# LCD_TouchBackLight.net
KiCad netlist of a schematic drawn in Altium Designer
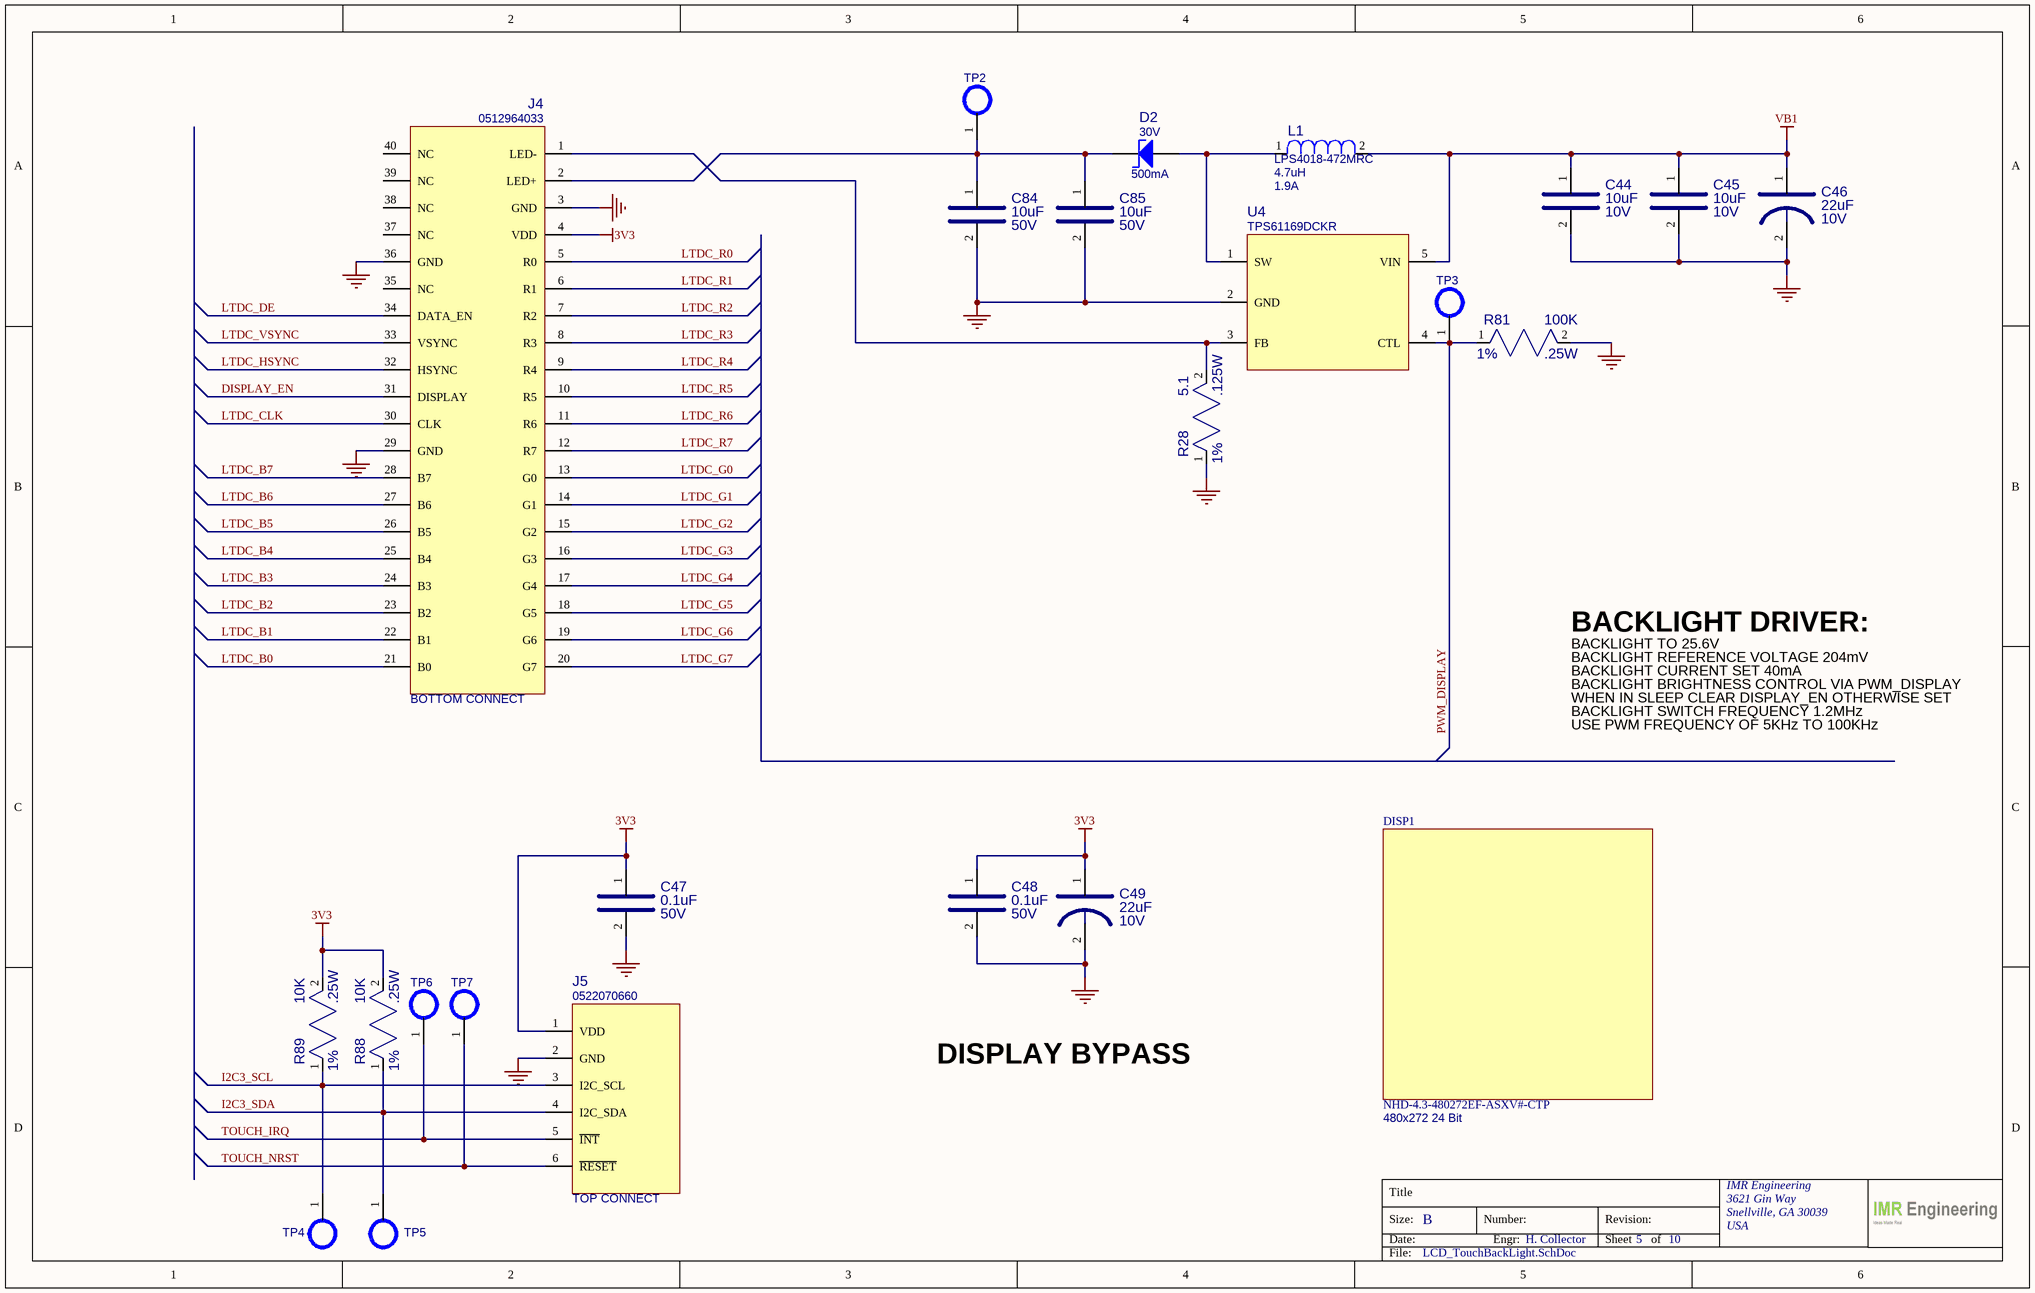
[diagram p0: LCD_TouchBackLight.SchDoc]

(export (version "E")
  (design (tool "Eeschema 10.0.6"))
  (components
    (comp (ref "C44")
      (value "10uF")
      (footprint "CAP_0805")
      (description "CAP CER 10UF 10V X7R 0805")
      (fields
        (field (name "MFG") "TDK Corporation")
        (field (name "TOLERANCE") "10%")
        (field (name "VOLTAGE") "10V")
      )
      (libsource (lib "IMR_Lib") (part "CAP_10UF_10V_0805"))
    )
    (comp (ref "C45")
      (value "10uF")
      (footprint "CAP_0805")
      (description "CAP CER 10UF 10V X7R 0805")
      (fields
        (field (name "MFG") "TDK Corporation")
        (field (name "TOLERANCE") "10%")
        (field (name "VOLTAGE") "10V")
      )
      (libsource (lib "IMR_Lib") (part "CAP_10UF_10V_0805"))
    )
    (comp (ref "C46")
      (value "22uF")
      (footprint "CAP_1206_TANT")
      (description "CAP TANT 22UF 20% 10V 1206")
      (fields
        (field (name "MFG") "AVX Corporation")
        (field (name "TOLERANCE") "10%")
        (field (name "VOLTAGE") "10V")
      )
      (libsource (lib "IMR_Lib") (part "CAP_22UF_10V_TANT"))
    )
    (comp (ref "C47")
      (value "0.1uF")
      (footprint "CAP_0805")
      (description "CAP CER 0.1UF 50V X7R 0805")
      (fields (field (name "MFG") "AVX") (field (name "TOLERANCE") "10%") (field (name "VOLTAGE") "50V"))
      (libsource (lib "IMR_Lib") (part "CAP_0.1UF_50V_0805"))
    )
    (comp (ref "C48")
      (value "0.1uF")
      (footprint "CAP_0805")
      (description "CAP CER 0.1UF 50V X7R 0805")
      (fields (field (name "MFG") "AVX") (field (name "TOLERANCE") "10%") (field (name "VOLTAGE") "50V"))
      (libsource (lib "IMR_Lib") (part "CAP_0.1UF_50V_0805"))
    )
    (comp (ref "C49")
      (value "22uF")
      (footprint "CAP_1206_TANT")
      (description "CAP TANT 22UF 20% 10V 1206")
      (fields
        (field (name "MFG") "AVX Corporation")
        (field (name "TOLERANCE") "10%")
        (field (name "VOLTAGE") "10V")
      )
      (libsource (lib "IMR_Lib") (part "CAP_22UF_10V_TANT"))
    )
    (comp (ref "C84")
      (value "10uF")
      (footprint "CAP_1206")
      (description "CAP CER 10UF 50V X5R 1206")
      (fields
        (field (name "MFG") "Samsung Electro-Mechanics")
        (field (name "TOLERANCE") "10%")
        (field (name "VOLTAGE") "50V")
      )
      (libsource (lib "IMR_Lib") (part "CAP_10UF_50V_1206"))
    )
    (comp (ref "C85")
      (value "10uF")
      (footprint "CAP_1206")
      (description "CAP CER 10UF 50V X5R 1206")
      (fields
        (field (name "MFG") "Samsung Electro-Mechanics")
        (field (name "TOLERANCE") "10%")
        (field (name "VOLTAGE") "50V")
      )
      (libsource (lib "IMR_Lib") (part "CAP_10UF_50V_1206"))
    )
    (comp (ref "D2")
      (value "30V")
      (footprint "SOD123")
      (description "DIODE SCHOTTKY 30V 500MA SOD123")
      (fields
        (field (name "MFG") "Nexperia USA Inc.")
        (field (name "CURRENT") "500mA")
        (field (name "Comment") "PMEG3005EGWJ")
      )
      (libsource (lib "IMR_Lib") (part "DIODE_SCHOTTKY_PMEG3005EGWJ"))
    )
    (comp (ref "DISP1")
      (value "NHD-4.3-480272EF-ASXV#-CTP")
      (footprint "NHD_NHD-4.3-480272EF-ASXV#-CTP")
      (description "LCD TFT 480X272 HIGH BRIGHT")
      (fields (field (name "MFG") "Newhaven Display Intl") (field (name "ALTIUM_VALUE") "480x272 24 Bit"))
      (libsource (lib "IMR_Lib") (part "MODULE_NHD-4.3-480272EF-ASXV#-CTP"))
    )
    (comp (ref "J4")
      (value "0512964033")
      (footprint "CONN_MOLEX_0512964033")
      (description "CONN FFC BOTTOM 40POS 0.50MM R/A")
      (fields (field (name "MFG") "Molex") (field (name "ALTIUM_VALUE") "BOTTOM CONNECT"))
      (libsource (lib "IMR_Lib") (part "CONN_MOLEX_0512964033"))
    )
    (comp (ref "J5")
      (value "0522070660")
      (footprint "CONN_MOLEX_0522070660")
      (description "CONN FPC TOP 6POS 1.00MM R/A")
      (fields (field (name "MFG") "Molex") (field (name "ALTIUM_VALUE") "TOP CONNECT"))
      (libsource (lib "IMR_Lib") (part "CONN_MOLEX_0522070660"))
    )
    (comp (ref "L1")
      (value "4.7uH")
      (footprint "LPS4018")
      (description "SHIELDED POWER INDUCTORS, 4.7UH")
      (fields
        (field (name "MFG") "COILCRAFT")
        (field (name "TOLERANCE") "20%")
        (field (name "MFG_PN") "LPS4018-472MRC")
        (field (name "CURRENT") "1.9A")
      )
      (libsource (lib "IMR_Lib") (part "INDUCTOR_LPS4018-472MRC"))
    )
    (comp (ref "R28")
      (value "5.1")
      (footprint "PMG_RES_0805")
      (description "RES 5.1 OHM 1% 1/8W 0805")
      (fields
        (field (name "MFG") "Yageo")
        (field (name "TOLERANCE") "1%")
        (field (name "POWER") ".125W")
        (field (name "Comment") "RC0805FR-075R1L")
      )
      (libsource (lib "IMR_Lib") (part "RES_5.1_0805_1/8W_1%"))
    )
    (comp (ref "R81")
      (value "100K")
      (footprint "PMG_RES_0805")
      (description "RES SMD 100K OHM 1% 1/4W 0805")
      (fields
        (field (name "MFG") "KOA Speer Electronics, Inc.")
        (field (name "TOLERANCE") "1%")
        (field (name "POWER") ".25W")
        (field (name "Comment") "RK73H2ATTD1003F")
      )
      (libsource (lib "IMR_Lib") (part "RES_100K_0805_1/4W_1%"))
    )
    (comp (ref "R88")
      (value "10K")
      (footprint "RES_0805")
      (description "RES SMD 10K OHM 1% 1/4W 0805")
      (fields
        (field (name "MFG") "KOA Speer Electronics, Inc.")
        (field (name "TOLERANCE") "1%")
        (field (name "POWER") ".25W")
        (field (name "Comment") "SG73S2ATTD1002F")
      )
      (libsource (lib "IMR_Lib") (part "RES_10K_0805_1/4W_1%"))
    )
    (comp (ref "R89")
      (value "10K")
      (footprint "RES_0805")
      (description "RES SMD 10K OHM 1% 1/4W 0805")
      (fields
        (field (name "MFG") "KOA Speer Electronics, Inc.")
        (field (name "TOLERANCE") "1%")
        (field (name "POWER") ".25W")
        (field (name "Comment") "SG73S2ATTD1002F")
      )
      (libsource (lib "IMR_Lib") (part "RES_10K_0805_1/4W_1%"))
    )
    (comp (ref "TP2")
      (value "TP_0635MM_HOLE")
      (footprint "TP_0635MM_HOLE")
      (description "3MM IN D. MT HOLE")
      (libsource (lib "IMR_Lib") (part "TP_0635MM_HOLE"))
    )
    (comp (ref "TP3")
      (value "TP_0635MM_HOLE")
      (footprint "TP_0635MM_HOLE")
      (description "3MM IN D. MT HOLE")
      (libsource (lib "IMR_Lib") (part "TP_0635MM_HOLE"))
    )
    (comp (ref "TP4")
      (value "TP_0635MM_HOLE")
      (footprint "TP_0635MM_HOLE")
      (description "3MM IN D. MT HOLE")
      (libsource (lib "IMR_Lib") (part "TP_0635MM_HOLE"))
    )
    (comp (ref "TP5")
      (value "TP_0635MM_HOLE")
      (footprint "TP_0635MM_HOLE")
      (description "3MM IN D. MT HOLE")
      (libsource (lib "IMR_Lib") (part "TP_0635MM_HOLE"))
    )
    (comp (ref "TP6")
      (value "TP_0635MM_HOLE")
      (footprint "TP_0635MM_HOLE")
      (description "3MM IN D. MT HOLE")
      (libsource (lib "IMR_Lib") (part "TP_0635MM_HOLE"))
    )
    (comp (ref "TP7")
      (value "TP_0635MM_HOLE")
      (footprint "TP_0635MM_HOLE")
      (description "3MM IN D. MT HOLE")
      (libsource (lib "IMR_Lib") (part "TP_0635MM_HOLE"))
    )
    (comp (ref "U4")
      (value "TPS61169DCKR")
      (footprint "SC70-5_SOT-353_5-TSSOP")
      (description "IC LED DRVR RGLTR DIM 1.8A SC70")
      (fields (field (name "MFG") "Texas Instruments") (field (name "MFG_PN") "TPS61169DCKR"))
      (libsource (lib "IMR_Lib") (part "IC_TPS61169DCKR"))
    )
  )
  (nets
    (net (code "1") (name "/DISPLAY_EN") (class "Default")
      (node (ref "J4") (pin "31") (pinfunction "DISPLAY_31") (pintype "passive"))
    )
    (net (code "2") (name "/I2C3_SCL") (class "Default")
      (node (ref "J5") (pin "3") (pinfunction "I2C_SCL_3") (pintype "passive"))
      (node (ref "R89") (pin "1") (pinfunction "1_1") (pintype "passive"))
      (node (ref "TP4") (pin "1") (pinfunction "1_1") (pintype "passive"))
    )
    (net (code "3") (name "/I2C3_SDA") (class "Default")
      (node (ref "J5") (pin "4") (pinfunction "I2C_SDA_4") (pintype "passive"))
      (node (ref "R88") (pin "1") (pinfunction "1_1") (pintype "passive"))
      (node (ref "TP5") (pin "1") (pinfunction "1_1") (pintype "passive"))
    )
    (net (code "4") (name "/LTDC_B0") (class "Default")
      (node (ref "J4") (pin "21") (pinfunction "B0_21") (pintype "passive"))
    )
    (net (code "5") (name "/LTDC_B1") (class "Default")
      (node (ref "J4") (pin "22") (pinfunction "B1_22") (pintype "passive"))
    )
    (net (code "6") (name "/LTDC_B2") (class "Default")
      (node (ref "J4") (pin "23") (pinfunction "B2_23") (pintype "passive"))
    )
    (net (code "7") (name "/LTDC_B3") (class "Default")
      (node (ref "J4") (pin "24") (pinfunction "B3_24") (pintype "passive"))
    )
    (net (code "8") (name "/LTDC_B4") (class "Default")
      (node (ref "J4") (pin "25") (pinfunction "B4_25") (pintype "passive"))
    )
    (net (code "9") (name "/LTDC_B5") (class "Default")
      (node (ref "J4") (pin "26") (pinfunction "B5_26") (pintype "passive"))
    )
    (net (code "10") (name "/LTDC_B6") (class "Default")
      (node (ref "J4") (pin "27") (pinfunction "B6_27") (pintype "passive"))
    )
    (net (code "11") (name "/LTDC_B7") (class "Default")
      (node (ref "J4") (pin "28") (pinfunction "B7_28") (pintype "passive"))
    )
    (net (code "12") (name "/LTDC_CLK") (class "Default")
      (node (ref "J4") (pin "30") (pinfunction "CLK_30") (pintype "passive"))
    )
    (net (code "13") (name "/LTDC_DE") (class "Default")
      (node (ref "J4") (pin "34") (pinfunction "DATA_EN_34") (pintype "passive"))
    )
    (net (code "14") (name "/LTDC_G0") (class "Default")
      (node (ref "J4") (pin "13") (pinfunction "G0_13") (pintype "passive"))
    )
    (net (code "15") (name "/LTDC_G1") (class "Default")
      (node (ref "J4") (pin "14") (pinfunction "G1_14") (pintype "passive"))
    )
    (net (code "16") (name "/LTDC_G2") (class "Default")
      (node (ref "J4") (pin "15") (pinfunction "G2_15") (pintype "passive"))
    )
    (net (code "17") (name "/LTDC_G3") (class "Default")
      (node (ref "J4") (pin "16") (pinfunction "G3_16") (pintype "passive"))
    )
    (net (code "18") (name "/LTDC_G4") (class "Default")
      (node (ref "J4") (pin "17") (pinfunction "G4_17") (pintype "passive"))
    )
    (net (code "19") (name "/LTDC_G5") (class "Default")
      (node (ref "J4") (pin "18") (pinfunction "G5_18") (pintype "passive"))
    )
    (net (code "20") (name "/LTDC_G6") (class "Default")
      (node (ref "J4") (pin "19") (pinfunction "G6_19") (pintype "passive"))
    )
    (net (code "21") (name "/LTDC_G7") (class "Default")
      (node (ref "J4") (pin "20") (pinfunction "G7_20") (pintype "passive"))
    )
    (net (code "22") (name "/LTDC_HSYNC") (class "Default")
      (node (ref "J4") (pin "32") (pinfunction "HSYNC_32") (pintype "passive"))
    )
    (net (code "23") (name "/LTDC_R0") (class "Default")
      (node (ref "J4") (pin "5") (pinfunction "R0_5") (pintype "passive"))
    )
    (net (code "24") (name "/LTDC_R1") (class "Default")
      (node (ref "J4") (pin "6") (pinfunction "R1_6") (pintype "passive"))
    )
    (net (code "25") (name "/LTDC_R2") (class "Default")
      (node (ref "J4") (pin "7") (pinfunction "R2_7") (pintype "passive"))
    )
    (net (code "26") (name "/LTDC_R3") (class "Default")
      (node (ref "J4") (pin "8") (pinfunction "R3_8") (pintype "passive"))
    )
    (net (code "27") (name "/LTDC_R4") (class "Default")
      (node (ref "J4") (pin "9") (pinfunction "R4_9") (pintype "passive"))
    )
    (net (code "28") (name "/LTDC_R5") (class "Default")
      (node (ref "J4") (pin "10") (pinfunction "R5_10") (pintype "passive"))
    )
    (net (code "29") (name "/LTDC_R6") (class "Default")
      (node (ref "J4") (pin "11") (pinfunction "R6_11") (pintype "passive"))
    )
    (net (code "30") (name "/LTDC_R7") (class "Default")
      (node (ref "J4") (pin "12") (pinfunction "R7_12") (pintype "passive"))
    )
    (net (code "31") (name "/LTDC_VSYNC") (class "Default")
      (node (ref "J4") (pin "33") (pinfunction "VSYNC_33") (pintype "passive"))
    )
    (net (code "32") (name "/PWM_DISPLAY") (class "Default")
      (node (ref "R81") (pin "1") (pinfunction "1_1") (pintype "passive"))
      (node (ref "TP3") (pin "1") (pinfunction "1_1") (pintype "passive"))
      (node (ref "U4") (pin "4") (pinfunction "CTL_4") (pintype "passive"))
    )
    (net (code "33") (name "/TOUCH_IRQ") (class "Default")
      (node (ref "J5") (pin "5") (pinfunction "INT_5") (pintype "passive"))
      (node (ref "TP6") (pin "1") (pinfunction "1_1") (pintype "passive"))
    )
    (net (code "34") (name "/TOUCH_NRST") (class "Default")
      (node (ref "J5") (pin "6") (pinfunction "RESET_6") (pintype "passive"))
      (node (ref "TP7") (pin "1") (pinfunction "1_1") (pintype "passive"))
    )
    (net (code "35") (name "3V3") (class "Default")
      (node (ref "C47") (pin "1") (pinfunction "1_1") (pintype "passive"))
      (node (ref "C48") (pin "1") (pinfunction "1_1") (pintype "passive"))
      (node (ref "C49") (pin "1") (pinfunction "1_1") (pintype "passive"))
      (node (ref "J4") (pin "4") (pinfunction "VDD_4") (pintype "passive"))
      (node (ref "J5") (pin "1") (pinfunction "VDD_1") (pintype "passive"))
      (node (ref "R88") (pin "2") (pinfunction "2_2") (pintype "passive"))
      (node (ref "R89") (pin "2") (pinfunction "2_2") (pintype "passive"))
    )
    (net (code "36") (name "GND") (class "Default")
      (node (ref "C44") (pin "2") (pinfunction "2_2") (pintype "passive"))
      (node (ref "C45") (pin "2") (pinfunction "2_2") (pintype "passive"))
      (node (ref "C46") (pin "2") (pinfunction "2_2") (pintype "passive"))
      (node (ref "C47") (pin "2") (pinfunction "2_2") (pintype "passive"))
      (node (ref "C48") (pin "2") (pinfunction "2_2") (pintype "passive"))
      (node (ref "C49") (pin "2") (pinfunction "2_2") (pintype "passive"))
      (node (ref "C84") (pin "2") (pinfunction "2_2") (pintype "passive"))
      (node (ref "C85") (pin "2") (pinfunction "2_2") (pintype "passive"))
      (node (ref "J4") (pin "29") (pinfunction "GND_29") (pintype "passive"))
      (node (ref "J4") (pin "3") (pinfunction "GND_3") (pintype "passive"))
      (node (ref "J4") (pin "36") (pinfunction "GND_36") (pintype "passive"))
      (node (ref "J5") (pin "2") (pinfunction "GND_2") (pintype "passive"))
      (node (ref "R28") (pin "1") (pinfunction "1_1") (pintype "passive"))
      (node (ref "R81") (pin "2") (pinfunction "2_2") (pintype "passive"))
      (node (ref "U4") (pin "2") (pinfunction "GND_2") (pintype "passive"))
    )
    (net (code "37") (name "Net-(D2-A)") (class "Default")
      (node (ref "D2") (pin "1") (pinfunction "A_1") (pintype "passive"))
      (node (ref "L1") (pin "1") (pinfunction "1_1") (pintype "passive"))
      (node (ref "U4") (pin "1") (pinfunction "SW_1") (pintype "passive"))
    )
    (net (code "38") (name "Net-(D2-K)") (class "Default")
      (node (ref "C84") (pin "1") (pinfunction "1_1") (pintype "passive"))
      (node (ref "C85") (pin "1") (pinfunction "1_1") (pintype "passive"))
      (node (ref "D2") (pin "2") (pinfunction "K_2") (pintype "passive"))
      (node (ref "J4") (pin "2") (pinfunction "LED+_2") (pintype "passive"))
      (node (ref "TP2") (pin "1") (pinfunction "1_1") (pintype "passive"))
    )
    (net (code "39") (name "Net-(J4-LED-)") (class "Default")
      (node (ref "J4") (pin "1") (pinfunction "LED-_1") (pintype "passive"))
      (node (ref "R28") (pin "2") (pinfunction "2_2") (pintype "passive"))
      (node (ref "U4") (pin "3") (pinfunction "FB_3") (pintype "passive"))
    )
    (net (code "40") (name "VB1") (class "Default")
      (node (ref "C44") (pin "1") (pinfunction "1_1") (pintype "passive"))
      (node (ref "C45") (pin "1") (pinfunction "1_1") (pintype "passive"))
      (node (ref "C46") (pin "1") (pinfunction "1_1") (pintype "passive"))
      (node (ref "L1") (pin "2") (pinfunction "2_2") (pintype "passive"))
      (node (ref "U4") (pin "5") (pinfunction "VIN_5") (pintype "passive"))
    )
    (net (code "41") (name "unconnected-(J4-NC-Pad35)") (class "Default")
      (node (ref "J4") (pin "35") (pinfunction "NC_35") (pintype "passive"))
    )
    (net (code "42") (name "unconnected-(J4-NC-Pad37)") (class "Default")
      (node (ref "J4") (pin "37") (pinfunction "NC_37") (pintype "passive"))
    )
    (net (code "43") (name "unconnected-(J4-NC-Pad38)") (class "Default")
      (node (ref "J4") (pin "38") (pinfunction "NC_38") (pintype "passive"))
    )
    (net (code "44") (name "unconnected-(J4-NC-Pad39)") (class "Default")
      (node (ref "J4") (pin "39") (pinfunction "NC_39") (pintype "passive"))
    )
    (net (code "45") (name "unconnected-(J4-NC-Pad40)") (class "Default")
      (node (ref "J4") (pin "40") (pinfunction "NC_40") (pintype "passive"))
    )
  )
)
